# Control_Board.net
KiCad netlist of a schematic drawn in EAGLE
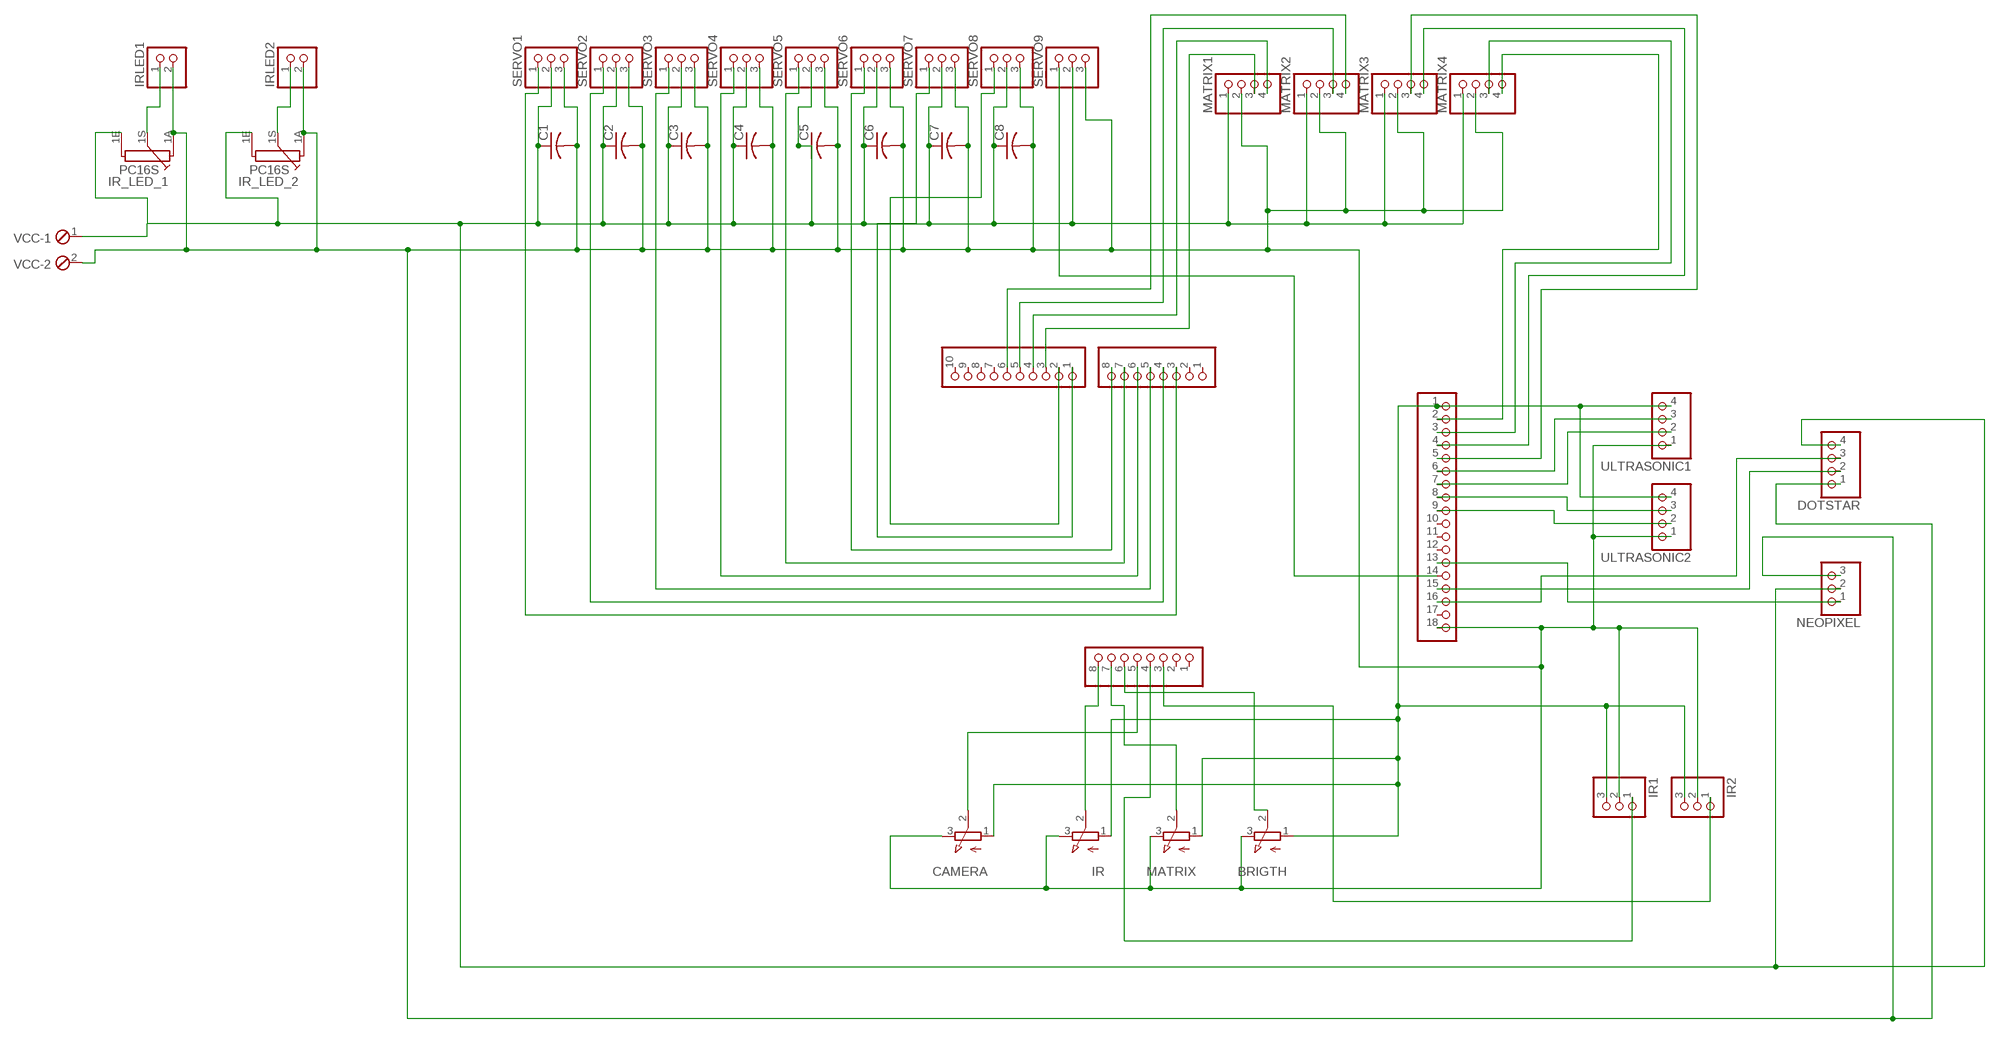
[diagram p0: schematic, sheet 1]

(export (version "E")
  (design (tool "Eeschema 10.0.6"))
  (components
    (comp (ref "BRIGTH")
      (value "3RP/1610N")
      (footprint "eagle-import:3RP_1610N")
      (libsource (lib "eagle-import") (part "3RP/1610N"))
    )
    (comp (ref "C1")
      (value "C-US050-030X075")
      (footprint "eagle-import:C050-030X075")
      (libsource (lib "eagle-import") (part "C-US050-030X075"))
    )
    (comp (ref "C2")
      (value "C-US050-030X075")
      (footprint "eagle-import:C050-030X075")
      (libsource (lib "eagle-import") (part "C-US050-030X075"))
    )
    (comp (ref "C3")
      (value "C-US050-030X075")
      (footprint "eagle-import:C050-030X075")
      (libsource (lib "eagle-import") (part "C-US050-030X075"))
    )
    (comp (ref "C4")
      (value "C-US050-030X075")
      (footprint "eagle-import:C050-030X075")
      (libsource (lib "eagle-import") (part "C-US050-030X075"))
    )
    (comp (ref "C5")
      (value "C-US050-030X075")
      (footprint "eagle-import:C050-030X075")
      (libsource (lib "eagle-import") (part "C-US050-030X075"))
    )
    (comp (ref "C6")
      (value "C-US050-030X075")
      (footprint "eagle-import:C050-030X075")
      (libsource (lib "eagle-import") (part "C-US050-030X075"))
    )
    (comp (ref "C7")
      (value "C-US050-030X075")
      (footprint "eagle-import:C050-030X075")
      (libsource (lib "eagle-import") (part "C-US050-030X075"))
    )
    (comp (ref "C8")
      (value "C-US050-030X075")
      (footprint "eagle-import:C050-030X075")
      (libsource (lib "eagle-import") (part "C-US050-030X075"))
    )
    (comp (ref "CAMERA")
      (value "3RP/1610N")
      (footprint "eagle-import:3RP_1610N")
      (libsource (lib "eagle-import") (part "3RP/1610N"))
    )
    (comp (ref "DOTSTAR")
      (value "PINHD-1X4")
      (footprint "eagle-import:1X04")
      (libsource (lib "eagle-import") (part "PINHD-1X4"))
    )
    (comp (ref "IR")
      (value "3RP/1610N")
      (footprint "eagle-import:3RP_1610N")
      (libsource (lib "eagle-import") (part "3RP/1610N"))
    )
    (comp (ref "IR1")
      (value "PINHD-1X3")
      (footprint "eagle-import:1X03")
      (libsource (lib "eagle-import") (part "PINHD-1X3"))
    )
    (comp (ref "IR2")
      (value "PINHD-1X3")
      (footprint "eagle-import:1X03")
      (libsource (lib "eagle-import") (part "PINHD-1X3"))
    )
    (comp (ref "IRLED1")
      (value "PINHD-1X2")
      (footprint "eagle-import:1X02")
      (libsource (lib "eagle-import") (part "PINHD-1X2"))
    )
    (comp (ref "IRLED2")
      (value "PINHD-1X2")
      (footprint "eagle-import:1X02")
      (libsource (lib "eagle-import") (part "PINHD-1X2"))
    )
    (comp (ref "IR_LED_1")
      (value "PC16S")
      (footprint "eagle-import:PC16S")
      (libsource (lib "eagle-import") (part "PC16S"))
    )
    (comp (ref "IR_LED_2")
      (value "PC16S")
      (footprint "eagle-import:PC16S")
      (libsource (lib "eagle-import") (part "PC16S"))
    )
    (comp (ref "MATRIX")
      (value "3RP/1610N")
      (footprint "eagle-import:3RP_1610N")
      (libsource (lib "eagle-import") (part "3RP/1610N"))
    )
    (comp (ref "MATRIX1")
      (value "PINHD-1X4")
      (footprint "eagle-import:1X04")
      (libsource (lib "eagle-import") (part "PINHD-1X4"))
    )
    (comp (ref "MATRIX2")
      (value "PINHD-1X4")
      (footprint "eagle-import:1X04")
      (libsource (lib "eagle-import") (part "PINHD-1X4"))
    )
    (comp (ref "MATRIX3")
      (value "PINHD-1X4")
      (footprint "eagle-import:1X04")
      (libsource (lib "eagle-import") (part "PINHD-1X4"))
    )
    (comp (ref "MATRIX4")
      (value "PINHD-1X4")
      (footprint "eagle-import:1X04")
      (libsource (lib "eagle-import") (part "PINHD-1X4"))
    )
    (comp (ref "MEGABOTTOMCENTER")
      (value "PINHD-1X8")
      (footprint "eagle-import:1X08")
      (libsource (lib "eagle-import") (part "PINHD-1X8"))
    )
    (comp (ref "MEGALATERAL")
      (value "PINHD-1X18")
      (footprint "eagle-import:1X18")
      (libsource (lib "eagle-import") (part "PINHD-1X18"))
    )
    (comp (ref "MEGATOPCENTER")
      (value "PINHD-1X8")
      (footprint "eagle-import:1X08")
      (libsource (lib "eagle-import") (part "PINHD-1X8"))
    )
    (comp (ref "MEGATOPLEFT")
      (value "PINHD-1X10_ARD")
      (footprint "eagle-import:1X10")
      (libsource (lib "eagle-import") (part "PINHD-1X10_ARD"))
    )
    (comp (ref "NEOPIXEL")
      (value "PINHD-1X3")
      (footprint "eagle-import:1X03")
      (libsource (lib "eagle-import") (part "PINHD-1X3"))
    )
    (comp (ref "SERVO1")
      (value "PINHD-1X3")
      (footprint "eagle-import:1X03")
      (libsource (lib "eagle-import") (part "PINHD-1X3"))
    )
    (comp (ref "SERVO2")
      (value "PINHD-1X3")
      (footprint "eagle-import:1X03")
      (libsource (lib "eagle-import") (part "PINHD-1X3"))
    )
    (comp (ref "SERVO3")
      (value "PINHD-1X3")
      (footprint "eagle-import:1X03")
      (libsource (lib "eagle-import") (part "PINHD-1X3"))
    )
    (comp (ref "SERVO4")
      (value "PINHD-1X3")
      (footprint "eagle-import:1X03")
      (libsource (lib "eagle-import") (part "PINHD-1X3"))
    )
    (comp (ref "SERVO5")
      (value "PINHD-1X3")
      (footprint "eagle-import:1X03")
      (libsource (lib "eagle-import") (part "PINHD-1X3"))
    )
    (comp (ref "SERVO6")
      (value "PINHD-1X3")
      (footprint "eagle-import:1X03")
      (libsource (lib "eagle-import") (part "PINHD-1X3"))
    )
    (comp (ref "SERVO7")
      (value "PINHD-1X3")
      (footprint "eagle-import:1X03")
      (libsource (lib "eagle-import") (part "PINHD-1X3"))
    )
    (comp (ref "SERVO8")
      (value "PINHD-1X3")
      (footprint "eagle-import:1X03")
      (libsource (lib "eagle-import") (part "PINHD-1X3"))
    )
    (comp (ref "SERVO9")
      (value "PINHD-1X3")
      (footprint "eagle-import:1X03")
      (libsource (lib "eagle-import") (part "PINHD-1X3"))
    )
    (comp (ref "ULTRASONIC1")
      (value "PINHD-1X4")
      (footprint "eagle-import:1X04")
      (libsource (lib "eagle-import") (part "PINHD-1X4"))
    )
    (comp (ref "ULTRASONIC2")
      (value "PINHD-1X4")
      (footprint "eagle-import:1X04")
      (libsource (lib "eagle-import") (part "PINHD-1X4"))
    )
    (comp (ref "VCC")
      (value "MPT2")
      (footprint "eagle-import:2POL254")
      (libsource (lib "eagle-import") (part "MPT2"))
    )
  )
  (nets
    (net (code "1") (name "Net-(BRIGTH-A)") (class "Default")
      (node (ref "BRIGTH") (pin "1") (pinfunction "A_1") (pintype "passive"))
      (node (ref "CAMERA") (pin "1") (pinfunction "A_1") (pintype "passive"))
      (node (ref "IR") (pin "1") (pinfunction "A_1") (pintype "passive"))
      (node (ref "IR1") (pin "3") (pinfunction "3_3") (pintype "passive"))
      (node (ref "IR2") (pin "3") (pinfunction "3_3") (pintype "passive"))
      (node (ref "MATRIX") (pin "1") (pinfunction "A_1") (pintype "passive"))
      (node (ref "MEGALATERAL") (pin "1") (pinfunction "1_1") (pintype "passive"))
      (node (ref "ULTRASONIC1") (pin "4") (pinfunction "4_4") (pintype "passive"))
      (node (ref "ULTRASONIC2") (pin "4") (pinfunction "4_4") (pintype "passive"))
    )
    (net (code "2") (name "Net-(BRIGTH-E)") (class "Default")
      (node (ref "BRIGTH") (pin "3") (pinfunction "E_3") (pintype "passive"))
      (node (ref "C1") (pin "2") (pinfunction "2_2") (pintype "passive"))
      (node (ref "C2") (pin "2") (pinfunction "2_2") (pintype "passive"))
      (node (ref "C3") (pin "2") (pinfunction "2_2") (pintype "passive"))
      (node (ref "C4") (pin "2") (pinfunction "2_2") (pintype "passive"))
      (node (ref "C5") (pin "2") (pinfunction "2_2") (pintype "passive"))
      (node (ref "C6") (pin "2") (pinfunction "2_2") (pintype "passive"))
      (node (ref "C7") (pin "2") (pinfunction "2_2") (pintype "passive"))
      (node (ref "C8") (pin "2") (pinfunction "2_2") (pintype "passive"))
      (node (ref "CAMERA") (pin "3") (pinfunction "E_3") (pintype "passive"))
      (node (ref "DOTSTAR") (pin "1") (pinfunction "1_1") (pintype "passive"))
      (node (ref "IR") (pin "3") (pinfunction "E_3") (pintype "passive"))
      (node (ref "IR1") (pin "2") (pinfunction "2_2") (pintype "passive"))
      (node (ref "IR2") (pin "2") (pinfunction "2_2") (pintype "passive"))
      (node (ref "IRLED1") (pin "2") (pinfunction "2_2") (pintype "passive"))
      (node (ref "IRLED2") (pin "2") (pinfunction "2_2") (pintype "passive"))
      (node (ref "IR_LED_1") (pin "1A") (pinfunction "1A_1A") (pintype "passive"))
      (node (ref "IR_LED_2") (pin "1A") (pinfunction "1A_1A") (pintype "passive"))
      (node (ref "MATRIX") (pin "3") (pinfunction "E_3") (pintype "passive"))
      (node (ref "MATRIX1") (pin "2") (pinfunction "2_2") (pintype "passive"))
      (node (ref "MATRIX2") (pin "2") (pinfunction "2_2") (pintype "passive"))
      (node (ref "MATRIX3") (pin "2") (pinfunction "2_2") (pintype "passive"))
      (node (ref "MATRIX4") (pin "2") (pinfunction "2_2") (pintype "passive"))
      (node (ref "MEGALATERAL") (pin "18") (pinfunction "18_18") (pintype "passive"))
      (node (ref "NEOPIXEL") (pin "3") (pinfunction "3_3") (pintype "passive"))
      (node (ref "SERVO1") (pin "3") (pinfunction "3_3") (pintype "passive"))
      (node (ref "SERVO2") (pin "3") (pinfunction "3_3") (pintype "passive"))
      (node (ref "SERVO3") (pin "3") (pinfunction "3_3") (pintype "passive"))
      (node (ref "SERVO4") (pin "3") (pinfunction "3_3") (pintype "passive"))
      (node (ref "SERVO5") (pin "3") (pinfunction "3_3") (pintype "passive"))
      (node (ref "SERVO6") (pin "3") (pinfunction "3_3") (pintype "passive"))
      (node (ref "SERVO7") (pin "3") (pinfunction "3_3") (pintype "passive"))
      (node (ref "SERVO8") (pin "3") (pinfunction "3_3") (pintype "passive"))
      (node (ref "SERVO9") (pin "3") (pinfunction "3_3") (pintype "passive"))
      (node (ref "ULTRASONIC1") (pin "1") (pinfunction "1_1") (pintype "passive"))
      (node (ref "ULTRASONIC2") (pin "1") (pinfunction "1_1") (pintype "passive"))
      (node (ref "VCC") (pin "2") (pinfunction "1_2") (pintype "passive"))
    )
    (net (code "3") (name "Net-(BRIGTH-S)") (class "Default")
      (node (ref "BRIGTH") (pin "2") (pinfunction "S_2") (pintype "passive"))
      (node (ref "MEGABOTTOMCENTER") (pin "6") (pinfunction "6_6") (pintype "passive"))
    )
    (net (code "4") (name "Net-(C1-Pad1)") (class "Default")
      (node (ref "C1") (pin "1") (pinfunction "1_1") (pintype "passive"))
      (node (ref "C2") (pin "1") (pinfunction "1_1") (pintype "passive"))
      (node (ref "C3") (pin "1") (pinfunction "1_1") (pintype "passive"))
      (node (ref "C4") (pin "1") (pinfunction "1_1") (pintype "passive"))
      (node (ref "C5") (pin "1") (pinfunction "1_1") (pintype "passive"))
      (node (ref "C6") (pin "1") (pinfunction "1_1") (pintype "passive"))
      (node (ref "C7") (pin "1") (pinfunction "1_1") (pintype "passive"))
      (node (ref "C8") (pin "1") (pinfunction "1_1") (pintype "passive"))
      (node (ref "DOTSTAR") (pin "4") (pinfunction "4_4") (pintype "passive"))
      (node (ref "IR_LED_1") (pin "1E") (pinfunction "1E_1E") (pintype "passive"))
      (node (ref "IR_LED_2") (pin "1E") (pinfunction "1E_1E") (pintype "passive"))
      (node (ref "MATRIX1") (pin "1") (pinfunction "1_1") (pintype "passive"))
      (node (ref "MATRIX2") (pin "1") (pinfunction "1_1") (pintype "passive"))
      (node (ref "MATRIX3") (pin "1") (pinfunction "1_1") (pintype "passive"))
      (node (ref "MATRIX4") (pin "1") (pinfunction "1_1") (pintype "passive"))
      (node (ref "NEOPIXEL") (pin "2") (pinfunction "2_2") (pintype "passive"))
      (node (ref "SERVO1") (pin "2") (pinfunction "2_2") (pintype "passive"))
      (node (ref "SERVO2") (pin "2") (pinfunction "2_2") (pintype "passive"))
      (node (ref "SERVO3") (pin "2") (pinfunction "2_2") (pintype "passive"))
      (node (ref "SERVO4") (pin "2") (pinfunction "2_2") (pintype "passive"))
      (node (ref "SERVO5") (pin "2") (pinfunction "2_2") (pintype "passive"))
      (node (ref "SERVO6") (pin "2") (pinfunction "2_2") (pintype "passive"))
      (node (ref "SERVO7") (pin "2") (pinfunction "2_2") (pintype "passive"))
      (node (ref "SERVO8") (pin "2") (pinfunction "2_2") (pintype "passive"))
      (node (ref "SERVO9") (pin "2") (pinfunction "2_2") (pintype "passive"))
      (node (ref "VCC") (pin "1") (pinfunction "1_1") (pintype "passive"))
    )
    (net (code "5") (name "Net-(CAMERA-S)") (class "Default")
      (node (ref "CAMERA") (pin "2") (pinfunction "S_2") (pintype "passive"))
      (node (ref "MEGABOTTOMCENTER") (pin "5") (pinfunction "5_5") (pintype "passive"))
    )
    (net (code "6") (name "Net-(DOTSTAR-Pad2)") (class "Default")
      (node (ref "DOTSTAR") (pin "2") (pinfunction "2_2") (pintype "passive"))
      (node (ref "MEGALATERAL") (pin "15") (pinfunction "15_15") (pintype "passive"))
    )
    (net (code "7") (name "Net-(DOTSTAR-Pad3)") (class "Default")
      (node (ref "DOTSTAR") (pin "3") (pinfunction "3_3") (pintype "passive"))
      (node (ref "MEGALATERAL") (pin "16") (pinfunction "16_16") (pintype "passive"))
    )
    (net (code "8") (name "Net-(IR-S)") (class "Default")
      (node (ref "IR") (pin "2") (pinfunction "S_2") (pintype "passive"))
      (node (ref "MEGABOTTOMCENTER") (pin "8") (pinfunction "8_8") (pintype "passive"))
    )
    (net (code "9") (name "Net-(IR1-Pad1)") (class "Default")
      (node (ref "IR1") (pin "1") (pinfunction "1_1") (pintype "passive"))
      (node (ref "MEGABOTTOMCENTER") (pin "4") (pinfunction "4_4") (pintype "passive"))
    )
    (net (code "10") (name "Net-(IR2-Pad1)") (class "Default")
      (node (ref "IR2") (pin "1") (pinfunction "1_1") (pintype "passive"))
      (node (ref "MEGABOTTOMCENTER") (pin "3") (pinfunction "3_3") (pintype "passive"))
    )
    (net (code "11") (name "Net-(IRLED1-Pad1)") (class "Default")
      (node (ref "IRLED1") (pin "1") (pinfunction "1_1") (pintype "passive"))
      (node (ref "IR_LED_1") (pin "1S") (pinfunction "1S_1S") (pintype "passive"))
    )
    (net (code "12") (name "Net-(IRLED2-Pad1)") (class "Default")
      (node (ref "IRLED2") (pin "1") (pinfunction "1_1") (pintype "passive"))
      (node (ref "IR_LED_2") (pin "1S") (pinfunction "1S_1S") (pintype "passive"))
    )
    (net (code "13") (name "Net-(MATRIX-S)") (class "Default")
      (node (ref "MATRIX") (pin "2") (pinfunction "S_2") (pintype "passive"))
      (node (ref "MEGABOTTOMCENTER") (pin "7") (pinfunction "7_7") (pintype "passive"))
    )
    (net (code "14") (name "Net-(MATRIX1-Pad3)") (class "Default")
      (node (ref "MATRIX1") (pin "3") (pinfunction "3_3") (pintype "passive"))
      (node (ref "MEGATOPLEFT") (pin "3") (pinfunction "3_3") (pintype "passive"))
    )
    (net (code "15") (name "Net-(MATRIX1-Pad4)") (class "Default")
      (node (ref "MATRIX1") (pin "4") (pinfunction "4_4") (pintype "passive"))
      (node (ref "MEGATOPLEFT") (pin "4") (pinfunction "4_4") (pintype "passive"))
    )
    (net (code "16") (name "Net-(MATRIX2-Pad3)") (class "Default")
      (node (ref "MATRIX2") (pin "3") (pinfunction "3_3") (pintype "passive"))
      (node (ref "MEGATOPLEFT") (pin "5") (pinfunction "5_5") (pintype "passive"))
    )
    (net (code "17") (name "Net-(MATRIX2-Pad4)") (class "Default")
      (node (ref "MATRIX2") (pin "4") (pinfunction "4_4") (pintype "passive"))
      (node (ref "MEGATOPLEFT") (pin "6") (pinfunction "6_6") (pintype "passive"))
    )
    (net (code "18") (name "Net-(MATRIX3-Pad3)") (class "Default")
      (node (ref "MATRIX3") (pin "3") (pinfunction "3_3") (pintype "passive"))
      (node (ref "MEGALATERAL") (pin "5") (pinfunction "5_5") (pintype "passive"))
    )
    (net (code "19") (name "Net-(MATRIX3-Pad4)") (class "Default")
      (node (ref "MATRIX3") (pin "4") (pinfunction "4_4") (pintype "passive"))
      (node (ref "MEGALATERAL") (pin "4") (pinfunction "4_4") (pintype "passive"))
    )
    (net (code "20") (name "Net-(MATRIX4-Pad3)") (class "Default")
      (node (ref "MATRIX4") (pin "3") (pinfunction "3_3") (pintype "passive"))
      (node (ref "MEGALATERAL") (pin "3") (pinfunction "3_3") (pintype "passive"))
    )
    (net (code "21") (name "Net-(MATRIX4-Pad4)") (class "Default")
      (node (ref "MATRIX4") (pin "4") (pinfunction "4_4") (pintype "passive"))
      (node (ref "MEGALATERAL") (pin "2") (pinfunction "2_2") (pintype "passive"))
    )
    (net (code "22") (name "Net-(MEGALATERAL-Pad6)") (class "Default")
      (node (ref "MEGALATERAL") (pin "6") (pinfunction "6_6") (pintype "passive"))
      (node (ref "ULTRASONIC1") (pin "3") (pinfunction "3_3") (pintype "passive"))
    )
    (net (code "23") (name "Net-(MEGALATERAL-Pad7)") (class "Default")
      (node (ref "MEGALATERAL") (pin "7") (pinfunction "7_7") (pintype "passive"))
      (node (ref "ULTRASONIC1") (pin "2") (pinfunction "2_2") (pintype "passive"))
    )
    (net (code "24") (name "Net-(MEGALATERAL-Pad8)") (class "Default")
      (node (ref "MEGALATERAL") (pin "8") (pinfunction "8_8") (pintype "passive"))
      (node (ref "ULTRASONIC2") (pin "3") (pinfunction "3_3") (pintype "passive"))
    )
    (net (code "25") (name "Net-(MEGALATERAL-Pad9)") (class "Default")
      (node (ref "MEGALATERAL") (pin "9") (pinfunction "9_9") (pintype "passive"))
      (node (ref "ULTRASONIC2") (pin "2") (pinfunction "2_2") (pintype "passive"))
    )
    (net (code "26") (name "Net-(MEGALATERAL-Pad13)") (class "Default")
      (node (ref "MEGALATERAL") (pin "13") (pinfunction "13_13") (pintype "passive"))
      (node (ref "NEOPIXEL") (pin "1") (pinfunction "1_1") (pintype "passive"))
    )
    (net (code "27") (name "Net-(MEGALATERAL-Pad14)") (class "Default")
      (node (ref "MEGALATERAL") (pin "14") (pinfunction "14_14") (pintype "passive"))
      (node (ref "SERVO9") (pin "1") (pinfunction "1_1") (pintype "passive"))
    )
    (net (code "28") (name "Net-(MEGATOPCENTER-Pad3)") (class "Default")
      (node (ref "MEGATOPCENTER") (pin "3") (pinfunction "3_3") (pintype "passive"))
      (node (ref "SERVO1") (pin "1") (pinfunction "1_1") (pintype "passive"))
    )
    (net (code "29") (name "Net-(MEGATOPCENTER-Pad4)") (class "Default")
      (node (ref "MEGATOPCENTER") (pin "4") (pinfunction "4_4") (pintype "passive"))
      (node (ref "SERVO2") (pin "1") (pinfunction "1_1") (pintype "passive"))
    )
    (net (code "30") (name "Net-(MEGATOPCENTER-Pad5)") (class "Default")
      (node (ref "MEGATOPCENTER") (pin "5") (pinfunction "5_5") (pintype "passive"))
      (node (ref "SERVO3") (pin "1") (pinfunction "1_1") (pintype "passive"))
    )
    (net (code "31") (name "Net-(MEGATOPCENTER-Pad6)") (class "Default")
      (node (ref "MEGATOPCENTER") (pin "6") (pinfunction "6_6") (pintype "passive"))
      (node (ref "SERVO4") (pin "1") (pinfunction "1_1") (pintype "passive"))
    )
    (net (code "32") (name "Net-(MEGATOPCENTER-Pad7)") (class "Default")
      (node (ref "MEGATOPCENTER") (pin "7") (pinfunction "7_7") (pintype "passive"))
      (node (ref "SERVO5") (pin "1") (pinfunction "1_1") (pintype "passive"))
    )
    (net (code "33") (name "Net-(MEGATOPCENTER-Pad8)") (class "Default")
      (node (ref "MEGATOPCENTER") (pin "8") (pinfunction "8_8") (pintype "passive"))
      (node (ref "SERVO6") (pin "1") (pinfunction "1_1") (pintype "passive"))
    )
    (net (code "34") (name "Net-(MEGATOPLEFT-Pad1)") (class "Default")
      (node (ref "MEGATOPLEFT") (pin "1") (pinfunction "1_1") (pintype "passive"))
      (node (ref "SERVO7") (pin "1") (pinfunction "1_1") (pintype "passive"))
    )
    (net (code "35") (name "Net-(MEGATOPLEFT-Pad2)") (class "Default")
      (node (ref "MEGATOPLEFT") (pin "2") (pinfunction "2_2") (pintype "passive"))
      (node (ref "SERVO8") (pin "1") (pinfunction "1_1") (pintype "passive"))
    )
    (net (code "36") (name "unconnected-(MEGABOTTOMCENTER-Pad1)") (class "Default")
      (node (ref "MEGABOTTOMCENTER") (pin "1") (pinfunction "1_1") (pintype "passive"))
    )
    (net (code "37") (name "unconnected-(MEGABOTTOMCENTER-Pad2)") (class "Default")
      (node (ref "MEGABOTTOMCENTER") (pin "2") (pinfunction "2_2") (pintype "passive"))
    )
    (net (code "38") (name "unconnected-(MEGALATERAL-Pad10)") (class "Default")
      (node (ref "MEGALATERAL") (pin "10") (pinfunction "10_10") (pintype "passive"))
    )
    (net (code "39") (name "unconnected-(MEGALATERAL-Pad11)") (class "Default")
      (node (ref "MEGALATERAL") (pin "11") (pinfunction "11_11") (pintype "passive"))
    )
    (net (code "40") (name "unconnected-(MEGALATERAL-Pad12)") (class "Default")
      (node (ref "MEGALATERAL") (pin "12") (pinfunction "12_12") (pintype "passive"))
    )
    (net (code "41") (name "unconnected-(MEGALATERAL-Pad17)") (class "Default")
      (node (ref "MEGALATERAL") (pin "17") (pinfunction "17_17") (pintype "passive"))
    )
    (net (code "42") (name "unconnected-(MEGATOPCENTER-Pad1)") (class "Default")
      (node (ref "MEGATOPCENTER") (pin "1") (pinfunction "1_1") (pintype "passive"))
    )
    (net (code "43") (name "unconnected-(MEGATOPCENTER-Pad2)") (class "Default")
      (node (ref "MEGATOPCENTER") (pin "2") (pinfunction "2_2") (pintype "passive"))
    )
    (net (code "44") (name "unconnected-(MEGATOPLEFT-Pad7)") (class "Default")
      (node (ref "MEGATOPLEFT") (pin "7") (pinfunction "7_7") (pintype "passive"))
    )
    (net (code "45") (name "unconnected-(MEGATOPLEFT-Pad8)") (class "Default")
      (node (ref "MEGATOPLEFT") (pin "8") (pinfunction "8_8") (pintype "passive"))
    )
    (net (code "46") (name "unconnected-(MEGATOPLEFT-Pad9)") (class "Default")
      (node (ref "MEGATOPLEFT") (pin "9") (pinfunction "9_9") (pintype "passive"))
    )
    (net (code "47") (name "unconnected-(MEGATOPLEFT-Pad10)") (class "Default")
      (node (ref "MEGATOPLEFT") (pin "10") (pinfunction "10_10") (pintype "passive"))
    )
  )
)
